# GPS_radiologger_v24_L70_CMWX_MAX.net
KiCad netlist of a schematic drawn in EAGLE
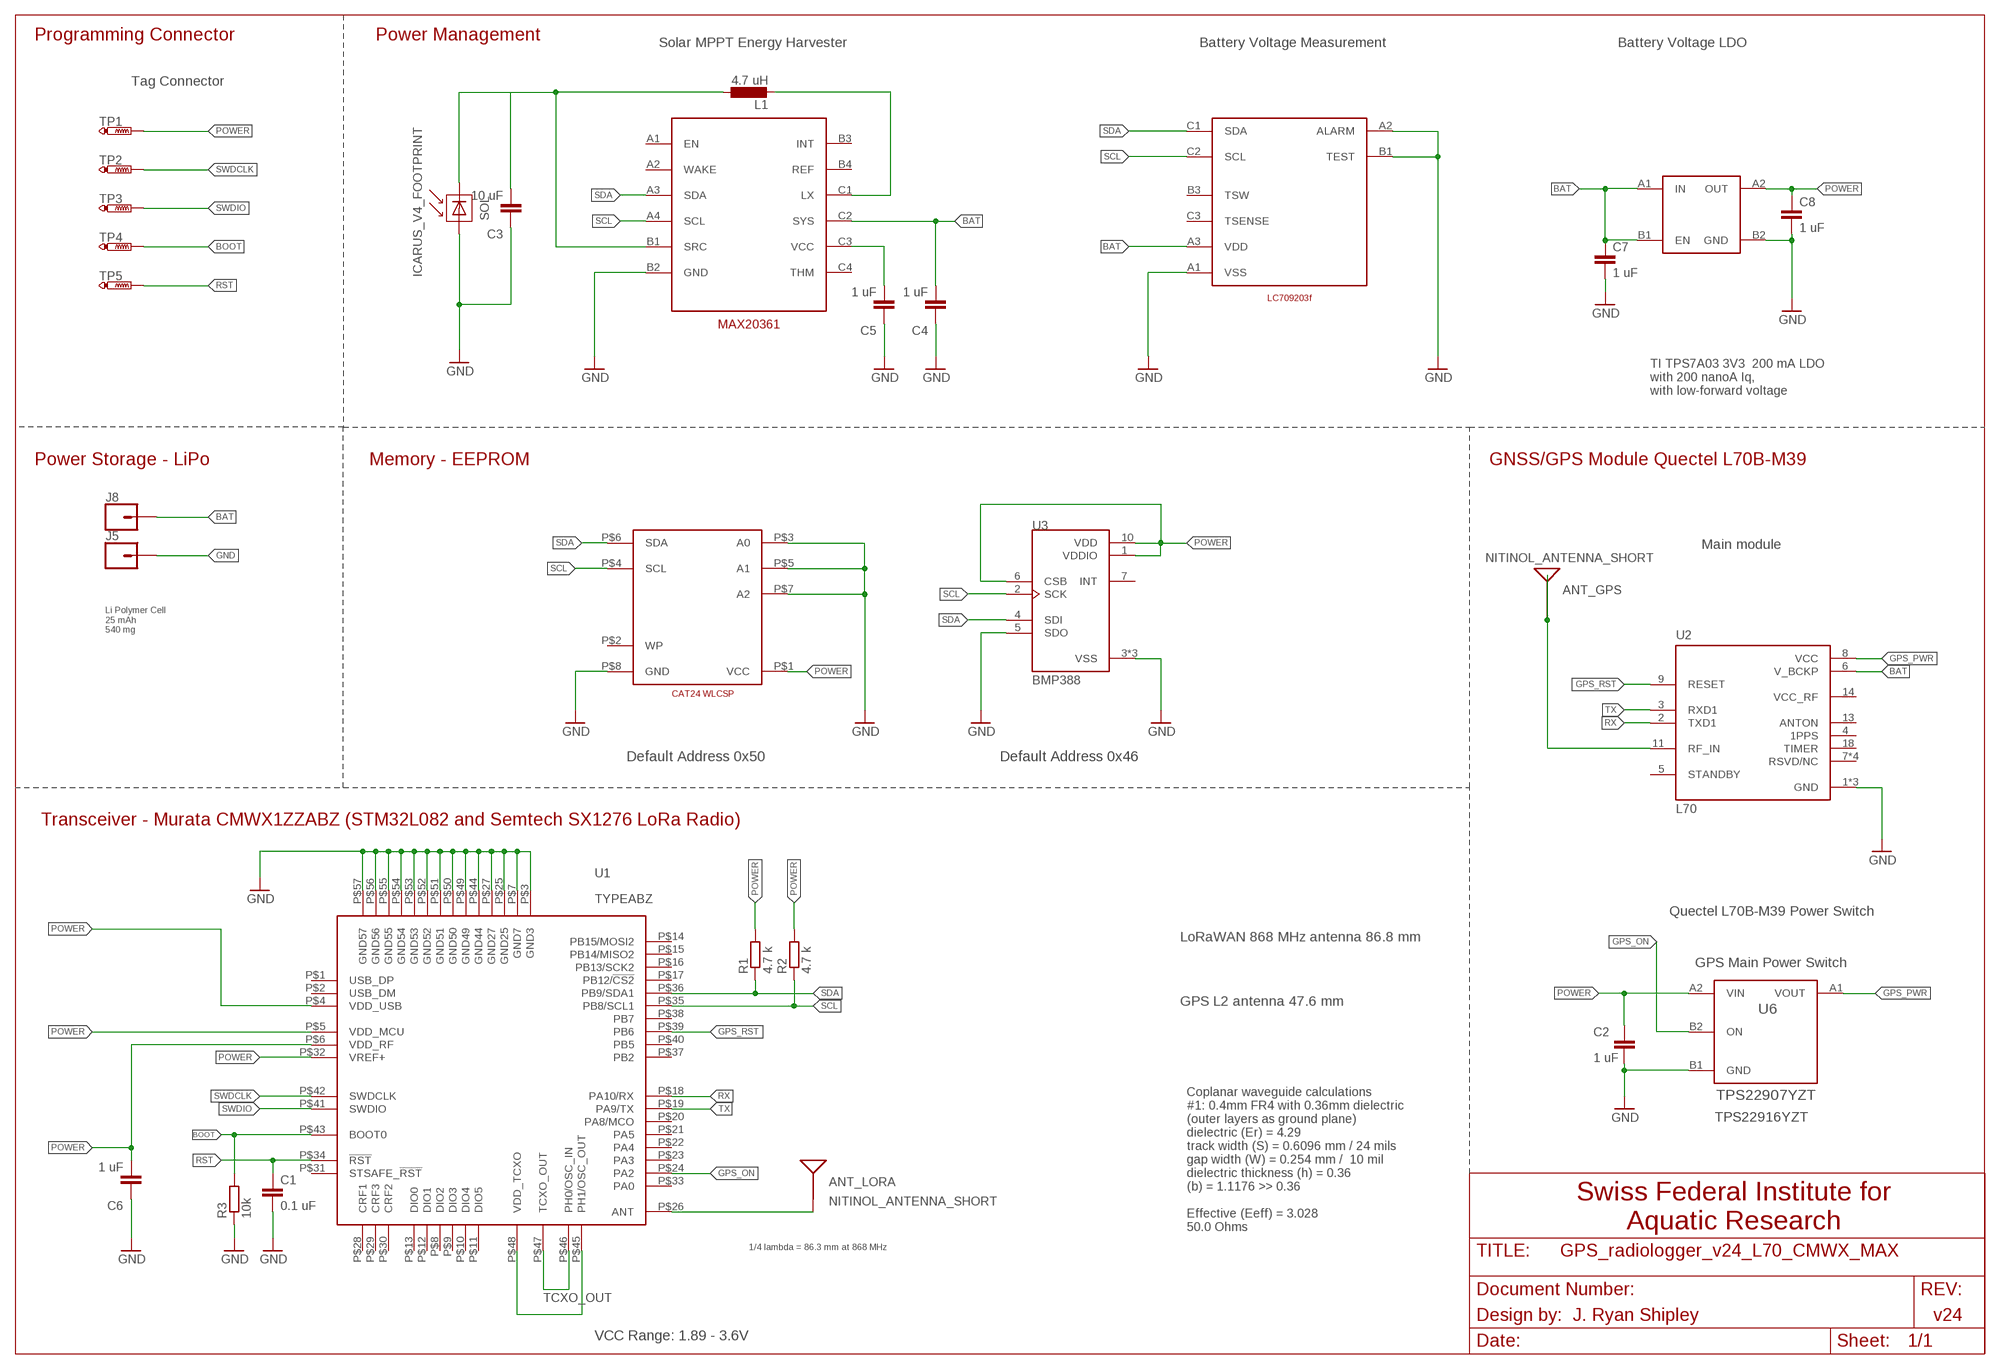
[diagram p0: schematic, sheet 1]

(export (version "E")
  (design (tool "Eeschema 10.0.6"))
  (components
    (comp (ref "ANT_GPS")
      (value "NITINOL_ANTENNA_SHORT")
      (footprint "eagle-import:ICARUS_NITINOL_ANTENNA_SHORT")
      (libsource (lib "eagle-import") (part "NITINOL_ANTENNA_SHORT"))
    )
    (comp (ref "ANT_LORA")
      (value "NITINOL_ANTENNA_SHORT")
      (footprint "eagle-import:ICARUS_NITINOL_ANTENNA_SHORT")
      (libsource (lib "eagle-import") (part "NITINOL_ANTENNA_SHORT"))
    )
    (comp (ref "C1")
      (value "0.1 uF")
      (footprint "eagle-import:C0201")
      (libsource (lib "eagle-import") (part "C-EUC0201"))
    )
    (comp (ref "C2")
      (value "1 uF")
      (footprint "eagle-import:C0201")
      (libsource (lib "eagle-import") (part "C-EUC0201"))
    )
    (comp (ref "C3")
      (value "10 uF")
      (footprint "eagle-import:C0402")
      (libsource (lib "eagle-import") (part "C-EUC0402"))
    )
    (comp (ref "C4")
      (value "1 uF")
      (footprint "eagle-import:C0201")
      (libsource (lib "eagle-import") (part "C-EUC0201"))
    )
    (comp (ref "C5")
      (value "1 uF")
      (footprint "eagle-import:C0201")
      (libsource (lib "eagle-import") (part "C-EUC0201"))
    )
    (comp (ref "C6")
      (value "1 uF")
      (footprint "eagle-import:C0201")
      (libsource (lib "eagle-import") (part "C-EUC0201"))
    )
    (comp (ref "C7")
      (value "1 uF")
      (footprint "eagle-import:0402-CAP")
      (libsource (lib "eagle-import") (part "0402CAP.KW"))
    )
    (comp (ref "C8")
      (value "1 uF")
      (footprint "eagle-import:0402-CAP")
      (libsource (lib "eagle-import") (part "0402CAP.KW"))
    )
    (comp (ref "J5")
      (value "CONN_01PTH_NO_SILK_SMALL")
      (footprint "eagle-import:1X01_SMALL")
      (libsource (lib "eagle-import") (part "CONN_01PTH_NO_SILK_SMALL"))
    )
    (comp (ref "J8")
      (value "CONN_01PTH_NO_SILK_SMALL")
      (footprint "eagle-import:1X01_SMALL")
      (libsource (lib "eagle-import") (part "CONN_01PTH_NO_SILK_SMALL"))
    )
    (comp (ref "L1")
      (value "4.7 uH")
      (footprint "eagle-import:INDC2016X120L")
      (libsource (lib "eagle-import") (part "IND_2016"))
    )
    (comp (ref "R1")
      (value "4.7 k")
      (footprint "eagle-import:R0201")
      (libsource (lib "eagle-import") (part "R-EU_R0201"))
    )
    (comp (ref "R2")
      (value "4.7 k")
      (footprint "eagle-import:R0201")
      (libsource (lib "eagle-import") (part "R-EU_R0201"))
    )
    (comp (ref "R3")
      (value "10k")
      (footprint "eagle-import:R0201")
      (libsource (lib "eagle-import") (part "R-EU_R0201"))
    )
    (comp (ref "SOL")
      (value "ICARUS_V4_FOOTPRINT")
      (footprint "eagle-import:ICARUS_FULL_FOOTPRINT")
      (libsource (lib "eagle-import") (part "ICARUS_V4_FOOTPRINT"))
    )
    (comp (ref "TP1")
      (value "PTR1TP08SQ")
      (footprint "eagle-import:TP08SQ")
      (libsource (lib "eagle-import") (part "PTR1TP08SQ"))
    )
    (comp (ref "TP2")
      (value "PTR1TP08SQ")
      (footprint "eagle-import:TP08SQ")
      (libsource (lib "eagle-import") (part "PTR1TP08SQ"))
    )
    (comp (ref "TP3")
      (value "PTR1TP08SQ")
      (footprint "eagle-import:TP08SQ")
      (libsource (lib "eagle-import") (part "PTR1TP08SQ"))
    )
    (comp (ref "TP4")
      (value "PTR1TP08SQ")
      (footprint "eagle-import:TP08SQ")
      (libsource (lib "eagle-import") (part "PTR1TP08SQ"))
    )
    (comp (ref "TP5")
      (value "PTR1TP08SQ")
      (footprint "eagle-import:TP08SQ")
      (libsource (lib "eagle-import") (part "PTR1TP08SQ"))
    )
    (comp (ref "U1")
      (value "TYPEABZ")
      (footprint "eagle-import:TYPEABZ")
      (libsource (lib "eagle-import") (part "TYPEABZ"))
    )
    (comp (ref "U2")
      (value "L70")
      (footprint "eagle-import:XCVR_L70")
      (fields (field (name "MF") "Quectel"))
      (libsource (lib "eagle-import") (part "L70"))
    )
    (comp (ref "U3")
      (value "BMP388")
      (footprint "eagle-import:PQFN50P200X200X80-10N")
      (fields (field (name "MF") "Bosch Sensortec"))
      (libsource (lib "eagle-import") (part "BMP388"))
    )
    (comp (ref "U4")
      (value "TPS7A03-DSBGA")
      (footprint "eagle-import:BGA4N35P2X2_70X70X40N")
      (libsource (lib "eagle-import") (part "TPS7A03-DSBGA"))
    )
    (comp (ref "U5")
      (value "LC709203F")
      (footprint "eagle-import:BGA9N50P3X3_160X175X50N")
      (libsource (lib "eagle-import") (part "LC709203F"))
    )
    (comp (ref "U6")
      (value "TPS22907YZT")
      (footprint "eagle-import:YFP0004-DSBGA")
      (libsource (lib "eagle-import") (part "TPS22907YZT"))
    )
    (comp (ref "U7")
      (value "CAT24_WLCSP8")
      (footprint "eagle-import:WLCSP8")
      (libsource (lib "eagle-import") (part "CAT24_WLCSP8"))
    )
    (comp (ref "U8")
      (value "MAX20361")
      (footprint "eagle-import:BGA12N40P4X3_123X163X64N")
      (libsource (lib "eagle-import") (part "MAX20361"))
    )
  )
  (nets
    (net (code "1") (name "/TCXO_OUT") (class "Default")
      (node (ref "U1") (pin "P$46") (pinfunction "PH0/OSC_IN_P$46") (pintype "bidirectional"))
      (node (ref "U1") (pin "P$47") (pinfunction "TCXO_OUT_P$47") (pintype "bidirectional"))
    )
    (net (code "2") (name "BAT") (class "Default")
      (node (ref "C4") (pin "2") (pinfunction "2_2") (pintype "passive"))
      (node (ref "C7") (pin "1") (pinfunction "1_1") (pintype "passive"))
      (node (ref "J8") (pin "P$1") (pinfunction "1_P$1") (pintype "passive"))
      (node (ref "U2") (pin "6") (pinfunction "V_BCKP_6") (pintype "power_in"))
      (node (ref "U4") (pin "A1") (pinfunction "IN_A1") (pintype "bidirectional"))
      (node (ref "U4") (pin "B1") (pinfunction "EN_B1") (pintype "bidirectional"))
      (node (ref "U5") (pin "A3") (pinfunction "VDD_A3") (pintype "bidirectional"))
      (node (ref "U8") (pin "C2") (pinfunction "SYS_C2") (pintype "bidirectional"))
    )
    (net (code "3") (name "BOOT") (class "Default")
      (node (ref "R3") (pin "2") (pinfunction "2_2") (pintype "passive"))
      (node (ref "TP4") (pin "TP") (pinfunction "TP_TP") (pintype "input"))
      (node (ref "U1") (pin "P$43") (pinfunction "BOOT0_P$43") (pintype "bidirectional"))
    )
    (net (code "4") (name "GND") (class "Default")
      (node (ref "C1") (pin "2") (pinfunction "2_2") (pintype "passive"))
      (node (ref "C2") (pin "2") (pinfunction "2_2") (pintype "passive"))
      (node (ref "C3") (pin "1") (pinfunction "1_1") (pintype "passive"))
      (node (ref "C4") (pin "1") (pinfunction "1_1") (pintype "passive"))
      (node (ref "C5") (pin "1") (pinfunction "1_1") (pintype "passive"))
      (node (ref "C6") (pin "1") (pinfunction "1_1") (pintype "passive"))
      (node (ref "C7") (pin "2") (pinfunction "2_2") (pintype "passive"))
      (node (ref "C8") (pin "2") (pinfunction "2_2") (pintype "passive"))
      (node (ref "J5") (pin "P$1") (pinfunction "1_P$1") (pintype "passive"))
      (node (ref "R3") (pin "1") (pinfunction "1_1") (pintype "passive"))
      (node (ref "SOL") (pin "P$2") (pinfunction "MINUS_P$2") (pintype "passive"))
      (node (ref "U1") (pin "P$25") (pinfunction "GND25_P$25") (pintype "power_in"))
      (node (ref "U1") (pin "P$27") (pinfunction "GND27_P$27") (pintype "power_in"))
      (node (ref "U1") (pin "P$3") (pinfunction "GND3_P$3") (pintype "power_in"))
      (node (ref "U1") (pin "P$44") (pinfunction "GND44_P$44") (pintype "power_in"))
      (node (ref "U1") (pin "P$49") (pinfunction "GND49_P$49") (pintype "power_in"))
      (node (ref "U1") (pin "P$50") (pinfunction "GND50_P$50") (pintype "power_in"))
      (node (ref "U1") (pin "P$51") (pinfunction "GND51_P$51") (pintype "power_in"))
      (node (ref "U1") (pin "P$52") (pinfunction "GND52_P$52") (pintype "power_in"))
      (node (ref "U1") (pin "P$53") (pinfunction "GND53_P$53") (pintype "power_in"))
      (node (ref "U1") (pin "P$54") (pinfunction "GND54_P$54") (pintype "power_in"))
      (node (ref "U1") (pin "P$55") (pinfunction "GND55_P$55") (pintype "power_in"))
      (node (ref "U1") (pin "P$56") (pinfunction "GND56_P$56") (pintype "power_in"))
      (node (ref "U1") (pin "P$57") (pinfunction "GND57_P$57") (pintype "power_in"))
      (node (ref "U1") (pin "P$7") (pinfunction "GND7_P$7") (pintype "power_in"))
      (node (ref "U2") (pin "1") (pinfunction "GND_1") (pintype "power_in"))
      (node (ref "U2") (pin "10") (pinfunction "GND_10") (pintype "power_in"))
      (node (ref "U2") (pin "12") (pinfunction "GND_12") (pintype "power_in"))
      (node (ref "U3") (pin "3") (pinfunction "VSS_3") (pintype "power_in"))
      (node (ref "U3") (pin "5") (pinfunction "SDO_5") (pintype "bidirectional"))
      (node (ref "U3") (pin "8") (pinfunction "VSS_8") (pintype "power_in"))
      (node (ref "U3") (pin "9") (pinfunction "VSS_9") (pintype "power_in"))
      (node (ref "U4") (pin "B2") (pinfunction "GND_B2") (pintype "bidirectional"))
      (node (ref "U5") (pin "A1") (pinfunction "VSS_A1") (pintype "bidirectional"))
      (node (ref "U5") (pin "A2") (pinfunction "ALARM_A2") (pintype "bidirectional"))
      (node (ref "U5") (pin "B1") (pinfunction "TEST_B1") (pintype "bidirectional"))
      (node (ref "U6") (pin "B1") (pinfunction "GND_B1") (pintype "bidirectional"))
      (node (ref "U7") (pin "P$3") (pinfunction "A0_P$3") (pintype "bidirectional"))
      (node (ref "U7") (pin "P$5") (pinfunction "A1_P$5") (pintype "bidirectional"))
      (node (ref "U7") (pin "P$7") (pinfunction "A2_P$7") (pintype "bidirectional"))
      (node (ref "U7") (pin "P$8") (pinfunction "GND_P$8") (pintype "bidirectional"))
      (node (ref "U8") (pin "B2") (pinfunction "GND_B2") (pintype "bidirectional"))
    )
    (net (code "5") (name "GPS_ON") (class "Default")
      (node (ref "U1") (pin "P$24") (pinfunction "PA2_P$24") (pintype "bidirectional"))
      (node (ref "U6") (pin "B2") (pinfunction "ON_B2") (pintype "bidirectional"))
    )
    (net (code "6") (name "GPS_PWR") (class "Default")
      (node (ref "U2") (pin "8") (pinfunction "VCC_8") (pintype "power_in"))
      (node (ref "U6") (pin "A1") (pinfunction "VOUT_A1") (pintype "bidirectional"))
    )
    (net (code "7") (name "GPS_RST") (class "Default")
      (node (ref "U1") (pin "P$39") (pinfunction "PB6_P$39") (pintype "bidirectional"))
      (node (ref "U2") (pin "9") (pinfunction "RESET_9") (pintype "input"))
    )
    (net (code "8") (name "Net-(SOL-PLUS)") (class "Default")
      (node (ref "C3") (pin "2") (pinfunction "2_2") (pintype "passive"))
      (node (ref "L1") (pin "1") (pinfunction "1_1") (pintype "passive"))
      (node (ref "SOL") (pin "P$1") (pinfunction "PLUS_P$1") (pintype "passive"))
      (node (ref "U8") (pin "B1") (pinfunction "SRC_B1") (pintype "bidirectional"))
    )
    (net (code "9") (name "Net-(U1-ANT)") (class "Default")
      (node (ref "ANT_LORA") (pin "1") (pinfunction "SIGNAL_1") (pintype "bidirectional"))
      (node (ref "ANT_LORA") (pin "2") (pinfunction "SIGNAL_2") (pintype "bidirectional"))
      (node (ref "ANT_LORA") (pin "3") (pinfunction "SIGNAL_3") (pintype "bidirectional"))
      (node (ref "U1") (pin "P$26") (pinfunction "ANT_P$26") (pintype "bidirectional"))
    )
    (net (code "10") (name "Net-(U1-PH1{slash}OSC_OUT)") (class "Default")
      (node (ref "U1") (pin "P$45") (pinfunction "PH1/OSC_OUT_P$45") (pintype "bidirectional"))
      (node (ref "U1") (pin "P$48") (pinfunction "VDD_TCXO_P$48") (pintype "power_in"))
    )
    (net (code "11") (name "Net-(U2-RF_IN)") (class "Default")
      (node (ref "ANT_GPS") (pin "1") (pinfunction "SIGNAL_1") (pintype "bidirectional"))
      (node (ref "ANT_GPS") (pin "2") (pinfunction "SIGNAL_2") (pintype "bidirectional"))
      (node (ref "ANT_GPS") (pin "3") (pinfunction "SIGNAL_3") (pintype "bidirectional"))
      (node (ref "U2") (pin "11") (pinfunction "RF_IN_11") (pintype "input"))
    )
    (net (code "12") (name "Net-(U8-LX)") (class "Default")
      (node (ref "L1") (pin "2") (pinfunction "2_2") (pintype "passive"))
      (node (ref "U8") (pin "C1") (pinfunction "LX_C1") (pintype "bidirectional"))
    )
    (net (code "13") (name "Net-(U8-VCC)") (class "Default")
      (node (ref "C5") (pin "2") (pinfunction "2_2") (pintype "passive"))
      (node (ref "U8") (pin "C3") (pinfunction "VCC_C3") (pintype "bidirectional"))
    )
    (net (code "14") (name "POWER") (class "Default")
      (node (ref "C2") (pin "1") (pinfunction "1_1") (pintype "passive"))
      (node (ref "C6") (pin "2") (pinfunction "2_2") (pintype "passive"))
      (node (ref "C8") (pin "1") (pinfunction "1_1") (pintype "passive"))
      (node (ref "R1") (pin "2") (pinfunction "2_2") (pintype "passive"))
      (node (ref "R2") (pin "2") (pinfunction "2_2") (pintype "passive"))
      (node (ref "TP1") (pin "TP") (pinfunction "TP_TP") (pintype "input"))
      (node (ref "U1") (pin "P$32") (pinfunction "VREF+_P$32") (pintype "power_in"))
      (node (ref "U1") (pin "P$4") (pinfunction "VDD_USB_P$4") (pintype "power_in"))
      (node (ref "U1") (pin "P$5") (pinfunction "VDD_MCU_P$5") (pintype "power_in"))
      (node (ref "U1") (pin "P$6") (pinfunction "VDD_RF_P$6") (pintype "power_in"))
      (node (ref "U3") (pin "1") (pinfunction "VDDIO_1") (pintype "power_in"))
      (node (ref "U3") (pin "10") (pinfunction "VDD_10") (pintype "power_in"))
      (node (ref "U3") (pin "6") (pinfunction "CSB_6") (pintype "input"))
      (node (ref "U4") (pin "A2") (pinfunction "OUT_A2") (pintype "bidirectional"))
      (node (ref "U6") (pin "A2") (pinfunction "VIN_A2") (pintype "bidirectional"))
      (node (ref "U7") (pin "P$1") (pinfunction "VCC_P$1") (pintype "bidirectional"))
    )
    (net (code "15") (name "RST") (class "Default")
      (node (ref "C1") (pin "1") (pinfunction "1_1") (pintype "passive"))
      (node (ref "TP5") (pin "TP") (pinfunction "TP_TP") (pintype "input"))
      (node (ref "U1") (pin "P$34") (pinfunction "~{RST}_P$34") (pintype "bidirectional"))
    )
    (net (code "16") (name "RX") (class "Default")
      (node (ref "U1") (pin "P$18") (pinfunction "PA10/RX_P$18") (pintype "bidirectional"))
      (node (ref "U2") (pin "2") (pinfunction "TXD1_2") (pintype "output"))
    )
    (net (code "17") (name "SCL") (class "Default")
      (node (ref "R2") (pin "1") (pinfunction "1_1") (pintype "passive"))
      (node (ref "U1") (pin "P$35") (pinfunction "PB8/SCL1_P$35") (pintype "bidirectional"))
      (node (ref "U3") (pin "2") (pinfunction "SCK_2") (pintype "input"))
      (node (ref "U5") (pin "C2") (pinfunction "SCL_C2") (pintype "bidirectional"))
      (node (ref "U7") (pin "P$4") (pinfunction "SCL_P$4") (pintype "bidirectional"))
      (node (ref "U8") (pin "A4") (pinfunction "SCL_A4") (pintype "bidirectional"))
    )
    (net (code "18") (name "SDA") (class "Default")
      (node (ref "R1") (pin "1") (pinfunction "1_1") (pintype "passive"))
      (node (ref "U1") (pin "P$36") (pinfunction "PB9/SDA1_P$36") (pintype "bidirectional"))
      (node (ref "U3") (pin "4") (pinfunction "SDI_4") (pintype "bidirectional"))
      (node (ref "U5") (pin "C1") (pinfunction "SDA_C1") (pintype "bidirectional"))
      (node (ref "U7") (pin "P$6") (pinfunction "SDA_P$6") (pintype "bidirectional"))
      (node (ref "U8") (pin "A3") (pinfunction "SDA_A3") (pintype "bidirectional"))
    )
    (net (code "19") (name "SWDCLK") (class "Default")
      (node (ref "TP2") (pin "TP") (pinfunction "TP_TP") (pintype "input"))
      (node (ref "U1") (pin "P$42") (pinfunction "SWDCLK_P$42") (pintype "bidirectional"))
    )
    (net (code "20") (name "SWDIO") (class "Default")
      (node (ref "TP3") (pin "TP") (pinfunction "TP_TP") (pintype "input"))
      (node (ref "U1") (pin "P$41") (pinfunction "SWDIO_P$41") (pintype "bidirectional"))
    )
    (net (code "21") (name "TX") (class "Default")
      (node (ref "U1") (pin "P$19") (pinfunction "PA9/TX_P$19") (pintype "bidirectional"))
      (node (ref "U2") (pin "3") (pinfunction "RXD1_3") (pintype "input"))
    )
    (net (code "22") (name "unconnected-(U1-CRF1-PadP$28)") (class "Default")
      (node (ref "U1") (pin "P$28") (pinfunction "CRF1_P$28") (pintype "no_connect"))
    )
    (net (code "23") (name "unconnected-(U1-CRF2-PadP$30)") (class "Default")
      (node (ref "U1") (pin "P$30") (pinfunction "CRF2_P$30") (pintype "no_connect"))
    )
    (net (code "24") (name "unconnected-(U1-CRF3-PadP$29)") (class "Default")
      (node (ref "U1") (pin "P$29") (pinfunction "CRF3_P$29") (pintype "no_connect"))
    )
    (net (code "25") (name "unconnected-(U1-DIO0-PadP$13)") (class "Default")
      (node (ref "U1") (pin "P$13") (pinfunction "DIO0_P$13") (pintype "no_connect"))
    )
    (net (code "26") (name "unconnected-(U1-DIO1-PadP$12)") (class "Default")
      (node (ref "U1") (pin "P$12") (pinfunction "DIO1_P$12") (pintype "no_connect"))
    )
    (net (code "27") (name "unconnected-(U1-DIO2-PadP$8)") (class "Default")
      (node (ref "U1") (pin "P$8") (pinfunction "DIO2_P$8") (pintype "no_connect"))
    )
    (net (code "28") (name "unconnected-(U1-DIO3-PadP$9)") (class "Default")
      (node (ref "U1") (pin "P$9") (pinfunction "DIO3_P$9") (pintype "no_connect"))
    )
    (net (code "29") (name "unconnected-(U1-DIO4-PadP$10)") (class "Default")
      (node (ref "U1") (pin "P$10") (pinfunction "DIO4_P$10") (pintype "bidirectional"))
    )
    (net (code "30") (name "unconnected-(U1-DIO5-PadP$11)") (class "Default")
      (node (ref "U1") (pin "P$11") (pinfunction "DIO5_P$11") (pintype "bidirectional"))
    )
    (net (code "31") (name "unconnected-(U1-PA0-PadP$33)") (class "Default")
      (node (ref "U1") (pin "P$33") (pinfunction "PA0_P$33") (pintype "bidirectional"))
    )
    (net (code "32") (name "unconnected-(U1-PA3-PadP$23)") (class "Default")
      (node (ref "U1") (pin "P$23") (pinfunction "PA3_P$23") (pintype "bidirectional"))
    )
    (net (code "33") (name "unconnected-(U1-PA4-PadP$22)") (class "Default")
      (node (ref "U1") (pin "P$22") (pinfunction "PA4_P$22") (pintype "bidirectional"))
    )
    (net (code "34") (name "unconnected-(U1-PA5-PadP$21)") (class "Default")
      (node (ref "U1") (pin "P$21") (pinfunction "PA5_P$21") (pintype "bidirectional"))
    )
    (net (code "35") (name "unconnected-(U1-PA8{slash}MCO-PadP$20)") (class "Default")
      (node (ref "U1") (pin "P$20") (pinfunction "PA8/MCO_P$20") (pintype "bidirectional"))
    )
    (net (code "36") (name "unconnected-(U1-PB2-PadP$37)") (class "Default")
      (node (ref "U1") (pin "P$37") (pinfunction "PB2_P$37") (pintype "bidirectional"))
    )
    (net (code "37") (name "unconnected-(U1-PB5-PadP$40)") (class "Default")
      (node (ref "U1") (pin "P$40") (pinfunction "PB5_P$40") (pintype "bidirectional"))
    )
    (net (code "38") (name "unconnected-(U1-PB7-PadP$38)") (class "Default")
      (node (ref "U1") (pin "P$38") (pinfunction "PB7_P$38") (pintype "bidirectional"))
    )
    (net (code "39") (name "unconnected-(U1-PB12{slash}~{CS2}-PadP$17)") (class "Default")
      (node (ref "U1") (pin "P$17") (pinfunction "PB12/~{CS2}_P$17") (pintype "bidirectional"))
    )
    (net (code "40") (name "unconnected-(U1-PB13{slash}SCK2-PadP$16)") (class "Default")
      (node (ref "U1") (pin "P$16") (pinfunction "PB13/SCK2_P$16") (pintype "bidirectional"))
    )
    (net (code "41") (name "unconnected-(U1-PB14{slash}MISO2-PadP$15)") (class "Default")
      (node (ref "U1") (pin "P$15") (pinfunction "PB14/MISO2_P$15") (pintype "bidirectional"))
    )
    (net (code "42") (name "unconnected-(U1-PB15{slash}MOSI2-PadP$14)") (class "Default")
      (node (ref "U1") (pin "P$14") (pinfunction "PB15/MOSI2_P$14") (pintype "bidirectional"))
    )
    (net (code "43") (name "unconnected-(U1-STSAFE_~{RST}-PadP$31)") (class "Default")
      (node (ref "U1") (pin "P$31") (pinfunction "STSAFE_~{RST}_P$31") (pintype "bidirectional"))
    )
    (net (code "44") (name "unconnected-(U1-USB_DM-PadP$2)") (class "Default")
      (node (ref "U1") (pin "P$2") (pinfunction "USB_DM_P$2") (pintype "bidirectional"))
    )
    (net (code "45") (name "unconnected-(U1-USB_DP-PadP$1)") (class "Default")
      (node (ref "U1") (pin "P$1") (pinfunction "USB_DP_P$1") (pintype "bidirectional"))
    )
    (net (code "46") (name "unconnected-(U2-1PPS-Pad4)") (class "Default")
      (node (ref "U2") (pin "4") (pinfunction "1PPS_4") (pintype "output"))
    )
    (net (code "47") (name "unconnected-(U2-ANTON-Pad13)") (class "Default")
      (node (ref "U2") (pin "13") (pinfunction "ANTON_13") (pintype "output"))
    )
    (net (code "48") (name "unconnected-(U2-RSVD{slash}NC-Pad7)") (class "Default")
      (node (ref "U2") (pin "7") (pinfunction "RSVD/NC_7") (pintype "no_connect"))
    )
    (net (code "49") (name "unconnected-(U2-RSVD{slash}NC-Pad15)") (class "Default")
      (node (ref "U2") (pin "15") (pinfunction "RSVD/NC_15") (pintype "no_connect"))
    )
    (net (code "50") (name "unconnected-(U2-RSVD{slash}NC-Pad16)") (class "Default")
      (node (ref "U2") (pin "16") (pinfunction "RSVD/NC_16") (pintype "no_connect"))
    )
    (net (code "51") (name "unconnected-(U2-RSVD{slash}NC-Pad17)") (class "Default")
      (node (ref "U2") (pin "17") (pinfunction "RSVD/NC_17") (pintype "no_connect"))
    )
    (net (code "52") (name "unconnected-(U2-STANDBY-Pad5)") (class "Default")
      (node (ref "U2") (pin "5") (pinfunction "STANDBY_5") (pintype "input"))
    )
    (net (code "53") (name "unconnected-(U2-TIMER-Pad18)") (class "Default")
      (node (ref "U2") (pin "18") (pinfunction "TIMER_18") (pintype "output"))
    )
    (net (code "54") (name "unconnected-(U2-VCC_RF-Pad14)") (class "Default")
      (node (ref "U2") (pin "14") (pinfunction "VCC_RF_14") (pintype "output"))
    )
    (net (code "55") (name "unconnected-(U3-INT-Pad7)") (class "Default")
      (node (ref "U3") (pin "7") (pinfunction "INT_7") (pintype "output"))
    )
    (net (code "56") (name "unconnected-(U5-TSENSE-PadC3)") (class "Default")
      (node (ref "U5") (pin "C3") (pinfunction "TSENSE_C3") (pintype "bidirectional"))
    )
    (net (code "57") (name "unconnected-(U5-TSW-PadB3)") (class "Default")
      (node (ref "U5") (pin "B3") (pinfunction "TSW_B3") (pintype "bidirectional"))
    )
    (net (code "58") (name "unconnected-(U7-WP-PadP$2)") (class "Default")
      (node (ref "U7") (pin "P$2") (pinfunction "WP_P$2") (pintype "bidirectional"))
    )
    (net (code "59") (name "unconnected-(U8-EN-PadA1)") (class "Default")
      (node (ref "U8") (pin "A1") (pinfunction "EN_A1") (pintype "bidirectional"))
    )
    (net (code "60") (name "unconnected-(U8-INT-PadB3)") (class "Default")
      (node (ref "U8") (pin "B3") (pinfunction "INT_B3") (pintype "bidirectional"))
    )
    (net (code "61") (name "unconnected-(U8-REF-PadB4)") (class "Default")
      (node (ref "U8") (pin "B4") (pinfunction "REF_B4") (pintype "bidirectional"))
    )
    (net (code "62") (name "unconnected-(U8-THM-PadC4)") (class "Default")
      (node (ref "U8") (pin "C4") (pinfunction "THM_C4") (pintype "bidirectional"))
    )
    (net (code "63") (name "unconnected-(U8-WAKE-PadA2)") (class "Default")
      (node (ref "U8") (pin "A2") (pinfunction "WAKE_A2") (pintype "bidirectional"))
    )
  )
)
